# SHDN-CURRENT-S11-V00-7SegmentDisplay.net
KiCad netlist of a schematic drawn in Altium Designer
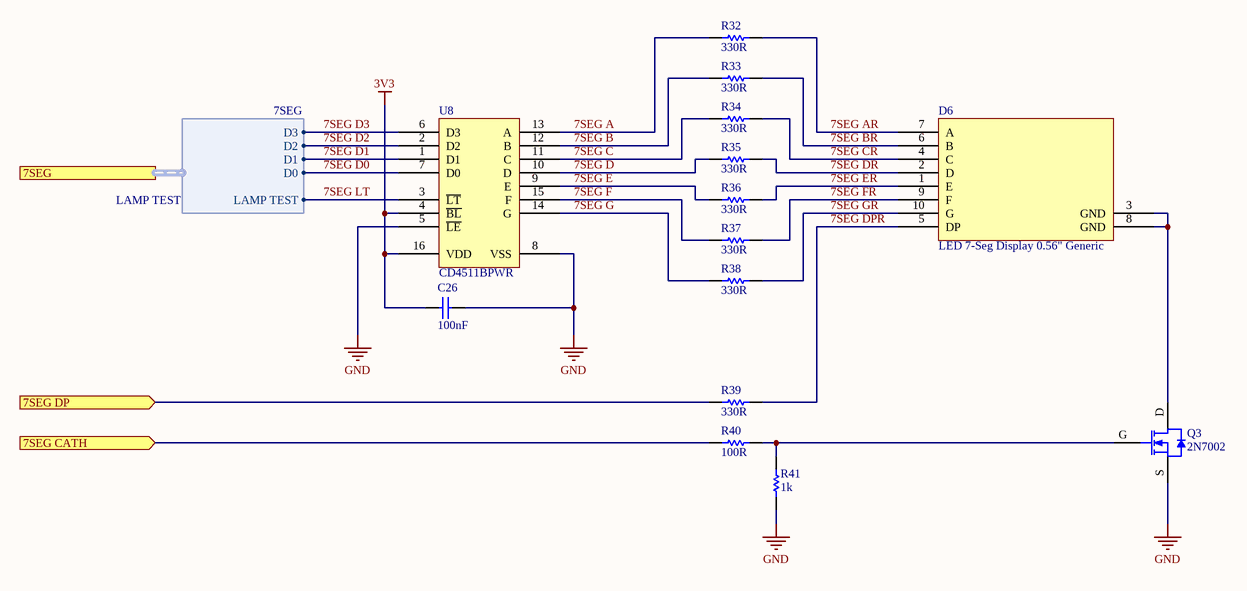
[diagram p0: SHDN-CURRENT-S11-V00-7SegmentDisplay.SchDoc]

(export (version "E")
  (design (tool "Eeschema 10.0.6"))
  (components
    (comp (ref "C26")
      (value "100nF")
      (footprint "Cap_Ceramic_0603")
      (description "Capacitor, Ceramic, SMD, 100nF, 50V, 5%, X7R, 0603")
      (libsource (lib "StandardCapacitors") (part "100nF 50V 5% X7R 0603"))
    )
    (comp (ref "D6")
      (value "LED 7-Seg Display 0.56\" Generic")
      (footprint "LED 7 SEG 0.56\"")
      (libsource (lib "QUTMS_LEDLibrary") (part "LED 7-Seg Display 0.56{dblquote}"))
    )
    (comp (ref "Q3")
      (value "2N7002")
      (footprint "SOT23-3")
      (libsource (lib "QUTMS_MOSFETLibrary") (part "2N7002"))
    )
    (comp (ref "R32")
      (value "330R")
      (footprint "Res_ThinFilm_0603")
      (description "Resistor, SMD, 330R, 0.1W, 5%, 0603")
      (libsource (lib "StandardResistors") (part "330R 5% 0603"))
    )
    (comp (ref "R33")
      (value "330R")
      (footprint "Res_ThinFilm_0603")
      (description "Resistor, SMD, 330R, 0.1W, 5%, 0603")
      (libsource (lib "StandardResistors") (part "330R 5% 0603"))
    )
    (comp (ref "R34")
      (value "330R")
      (footprint "Res_ThinFilm_0603")
      (description "Resistor, SMD, 330R, 0.1W, 5%, 0603")
      (libsource (lib "StandardResistors") (part "330R 5% 0603"))
    )
    (comp (ref "R35")
      (value "330R")
      (footprint "Res_ThinFilm_0603")
      (description "Resistor, SMD, 330R, 0.1W, 5%, 0603")
      (libsource (lib "StandardResistors") (part "330R 5% 0603"))
    )
    (comp (ref "R36")
      (value "330R")
      (footprint "Res_ThinFilm_0603")
      (description "Resistor, SMD, 330R, 0.1W, 5%, 0603")
      (libsource (lib "StandardResistors") (part "330R 5% 0603"))
    )
    (comp (ref "R37")
      (value "330R")
      (footprint "Res_ThinFilm_0603")
      (description "Resistor, SMD, 330R, 0.1W, 5%, 0603")
      (libsource (lib "StandardResistors") (part "330R 5% 0603"))
    )
    (comp (ref "R38")
      (value "330R")
      (footprint "Res_ThinFilm_0603")
      (description "Resistor, SMD, 330R, 0.1W, 5%, 0603")
      (libsource (lib "StandardResistors") (part "330R 5% 0603"))
    )
    (comp (ref "R39")
      (value "330R")
      (footprint "Res_ThinFilm_0603")
      (description "Resistor, SMD, 330R, 0.1W, 5%, 0603")
      (libsource (lib "StandardResistors") (part "330R 5% 0603"))
    )
    (comp (ref "R40")
      (value "100R")
      (footprint "Res_ThinFilm_0603")
      (description "Resistor, SMD, 100R, 0.1W, 5%, 0603")
      (libsource (lib "StandardResistors") (part "100R 5%, 0603"))
    )
    (comp (ref "R41")
      (value "1k")
      (footprint "Res_ThinFilm_0603")
      (description "Resistor, SMD, 1k, 0.1W, 5%, 0603")
      (libsource (lib "StandardResistors") (part "1k 5% 0603"))
    )
    (comp (ref "U8")
      (value "CD4511BPWR")
      (footprint "16-TSSOP")
      (description "LED Driver 7 Segment 16-TSSOP")
      (libsource (lib "QUTMS_LEDLibrary") (part "CD4511BPWR"))
    )
  )
  (nets
    (net (code "2") (name "/7SEG A") (class "Default")
      (node (ref "R32") (pin "1") (pinfunction "1_1") (pintype "passive"))
      (node (ref "U8") (pin "13") (pinfunction "A_13") (pintype "passive"))
    )
    (net (code "3") (name "/7SEG AR") (class "Default")
      (node (ref "D6") (pin "7") (pinfunction "A_7") (pintype "passive"))
      (node (ref "R32") (pin "2") (pinfunction "2_2") (pintype "passive"))
    )
    (net (code "4") (name "/7SEG B") (class "Default")
      (node (ref "R33") (pin "1") (pinfunction "1_1") (pintype "passive"))
      (node (ref "U8") (pin "12") (pinfunction "B_12") (pintype "passive"))
    )
    (net (code "5") (name "/7SEG BR") (class "Default")
      (node (ref "D6") (pin "6") (pinfunction "B_6") (pintype "passive"))
      (node (ref "R33") (pin "2") (pinfunction "2_2") (pintype "passive"))
    )
    (net (code "6") (name "/7SEG C") (class "Default")
      (node (ref "R34") (pin "1") (pinfunction "1_1") (pintype "passive"))
      (node (ref "U8") (pin "11") (pinfunction "C_11") (pintype "passive"))
    )
    (net (code "7") (name "/7SEG CATH") (class "Default")
      (node (ref "R40") (pin "1") (pinfunction "1_1") (pintype "passive"))
    )
    (net (code "8") (name "/7SEG CR") (class "Default")
      (node (ref "D6") (pin "4") (pinfunction "C_4") (pintype "passive"))
      (node (ref "R34") (pin "2") (pinfunction "2_2") (pintype "passive"))
    )
    (net (code "9") (name "/7SEG D") (class "Default")
      (node (ref "R35") (pin "1") (pinfunction "1_1") (pintype "passive"))
      (node (ref "U8") (pin "10") (pinfunction "D_10") (pintype "passive"))
    )
    (net (code "10") (name "/7SEG D0") (class "Default")
      (node (ref "U8") (pin "7") (pinfunction "D0_7") (pintype "passive"))
    )
    (net (code "11") (name "/7SEG D1") (class "Default")
      (node (ref "U8") (pin "1") (pinfunction "D1_1") (pintype "passive"))
    )
    (net (code "12") (name "/7SEG D2") (class "Default")
      (node (ref "U8") (pin "2") (pinfunction "D2_2") (pintype "passive"))
    )
    (net (code "13") (name "/7SEG D3") (class "Default")
      (node (ref "U8") (pin "6") (pinfunction "D3_6") (pintype "passive"))
    )
    (net (code "14") (name "/7SEG DP") (class "Default")
      (node (ref "R39") (pin "1") (pinfunction "1_1") (pintype "passive"))
    )
    (net (code "15") (name "/7SEG DPR") (class "Default")
      (node (ref "D6") (pin "5") (pinfunction "DP_5") (pintype "passive"))
      (node (ref "R39") (pin "2") (pinfunction "2_2") (pintype "passive"))
    )
    (net (code "16") (name "/7SEG DR") (class "Default")
      (node (ref "D6") (pin "2") (pinfunction "D_2") (pintype "passive"))
      (node (ref "R35") (pin "2") (pinfunction "2_2") (pintype "passive"))
    )
    (net (code "17") (name "/7SEG E") (class "Default")
      (node (ref "R36") (pin "1") (pinfunction "1_1") (pintype "passive"))
      (node (ref "U8") (pin "9") (pinfunction "E_9") (pintype "passive"))
    )
    (net (code "18") (name "/7SEG ER") (class "Default")
      (node (ref "D6") (pin "1") (pinfunction "E_1") (pintype "passive"))
      (node (ref "R36") (pin "2") (pinfunction "2_2") (pintype "passive"))
    )
    (net (code "19") (name "/7SEG F") (class "Default")
      (node (ref "R37") (pin "1") (pinfunction "1_1") (pintype "passive"))
      (node (ref "U8") (pin "15") (pinfunction "F_15") (pintype "passive"))
    )
    (net (code "20") (name "/7SEG FR") (class "Default")
      (node (ref "D6") (pin "9") (pinfunction "F_9") (pintype "passive"))
      (node (ref "R37") (pin "2") (pinfunction "2_2") (pintype "passive"))
    )
    (net (code "21") (name "/7SEG G") (class "Default")
      (node (ref "R38") (pin "1") (pinfunction "1_1") (pintype "passive"))
      (node (ref "U8") (pin "14") (pinfunction "G_14") (pintype "passive"))
    )
    (net (code "22") (name "/7SEG GR") (class "Default")
      (node (ref "D6") (pin "10") (pinfunction "G_10") (pintype "passive"))
      (node (ref "R38") (pin "2") (pinfunction "2_2") (pintype "passive"))
    )
    (net (code "23") (name "/7SEG LT") (class "Default")
      (node (ref "U8") (pin "3") (pinfunction "~{LT}_3") (pintype "passive"))
    )
    (net (code "25") (name "3V3") (class "Default")
      (node (ref "C26") (pin "1") (pinfunction "1_1") (pintype "passive"))
      (node (ref "U8") (pin "16") (pinfunction "VDD_16") (pintype "passive"))
      (node (ref "U8") (pin "4") (pinfunction "~{BL}_4") (pintype "passive"))
    )
    (net (code "26") (name "GND") (class "Default")
      (node (ref "C26") (pin "2") (pinfunction "2_2") (pintype "passive"))
      (node (ref "Q3") (pin "S") (pinfunction "S_S") (pintype "passive"))
      (node (ref "R41") (pin "1") (pinfunction "1_1") (pintype "passive"))
      (node (ref "U8") (pin "5") (pinfunction "~{LE}_5") (pintype "passive"))
      (node (ref "U8") (pin "8") (pinfunction "VSS_8") (pintype "passive"))
    )
    (net (code "27") (name "Net-(D6-GND-Pad3)") (class "Default")
      (node (ref "D6") (pin "3") (pinfunction "GND_3") (pintype "passive"))
      (node (ref "D6") (pin "8") (pinfunction "GND_8") (pintype "passive"))
      (node (ref "Q3") (pin "D") (pinfunction "D_D") (pintype "passive"))
    )
    (net (code "28") (name "Net-(Q3-PadG)") (class "Default")
      (node (ref "Q3") (pin "G") (pinfunction "G_G") (pintype "passive"))
      (node (ref "R40") (pin "2") (pinfunction "2_2") (pintype "passive"))
      (node (ref "R41") (pin "2") (pinfunction "2_2") (pintype "passive"))
    )
  )
)
